# Magnetic-Encoder-V01.net
KiCad netlist of a schematic drawn in Altium Designer
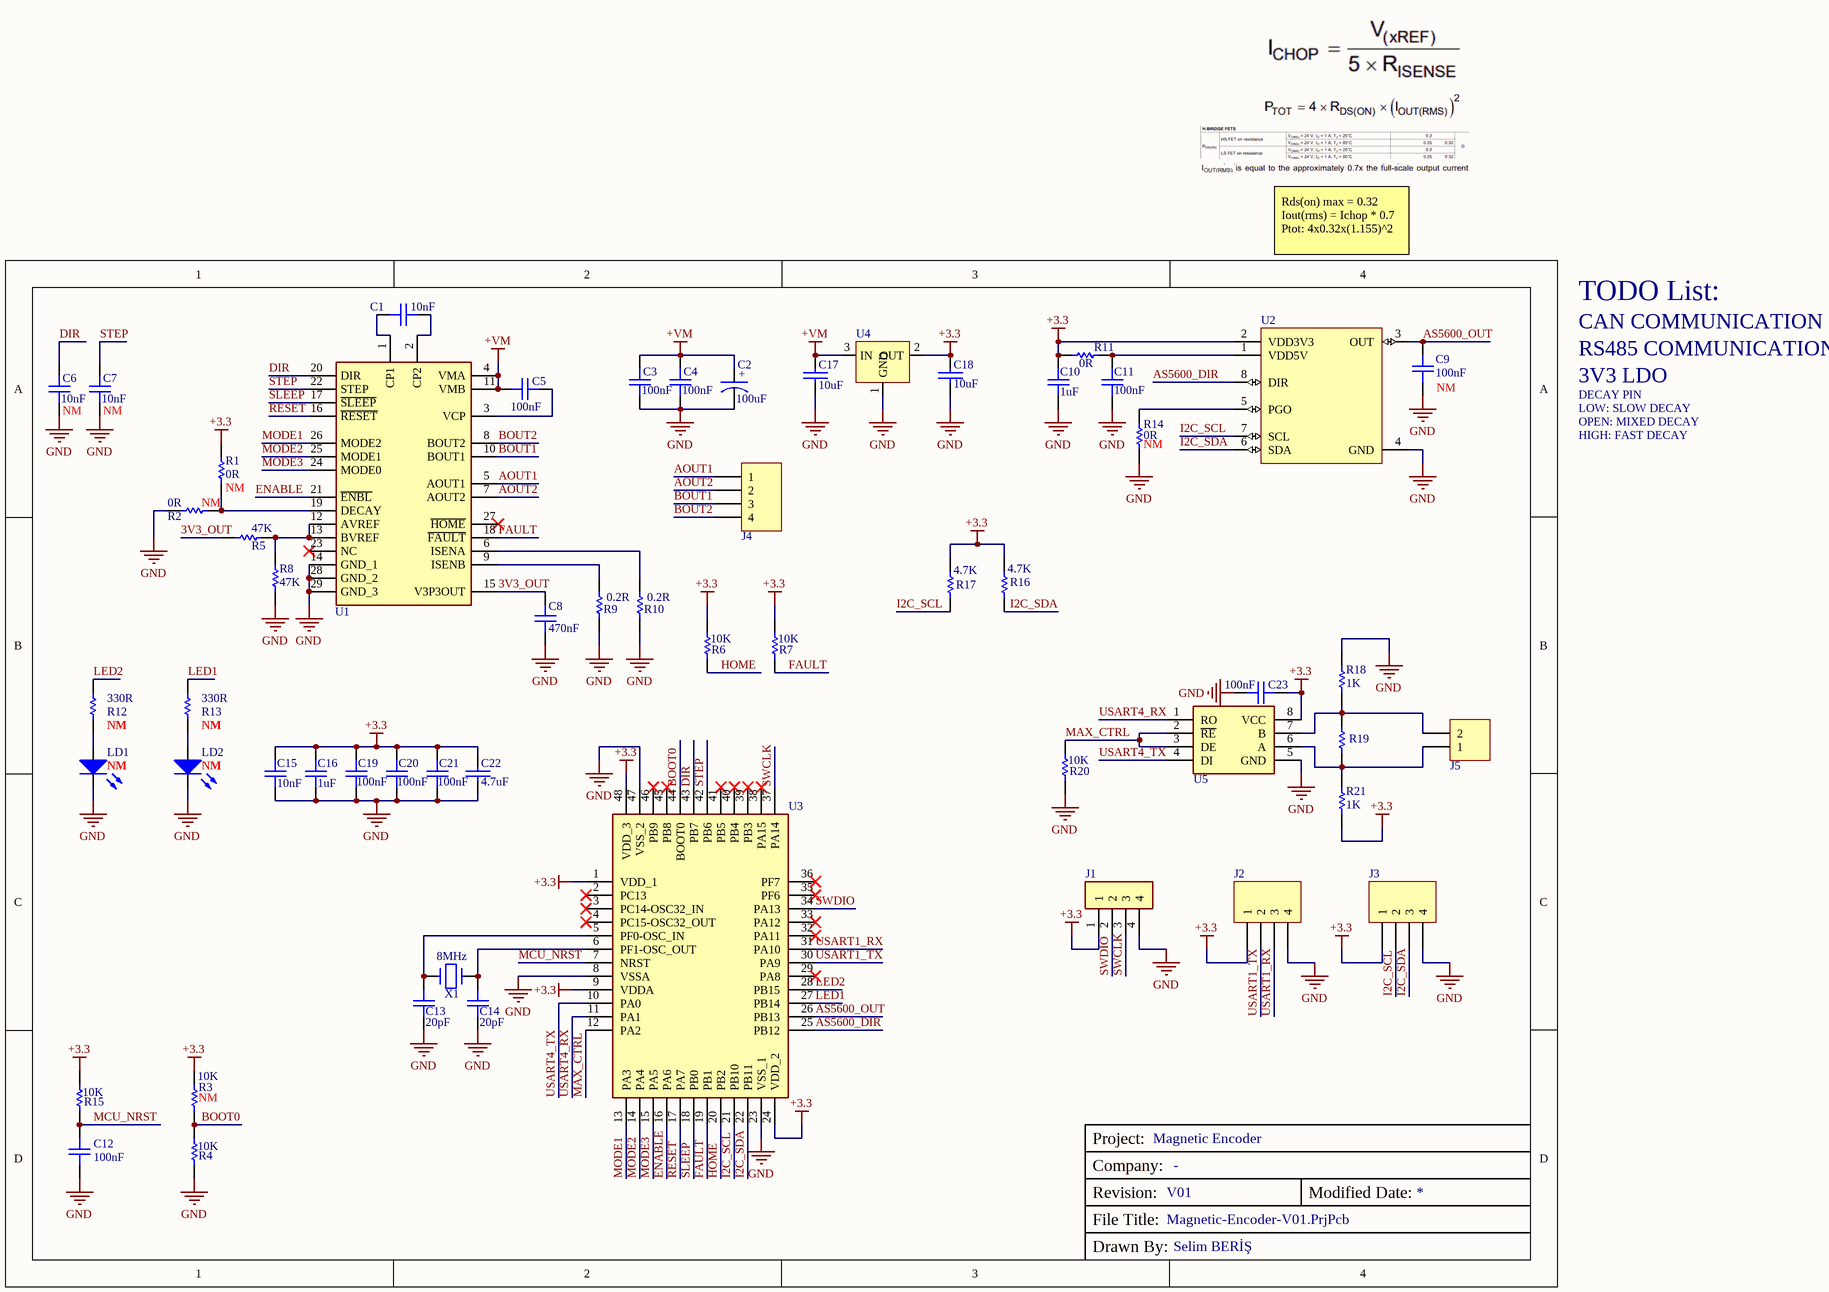
[diagram p0: Magnetic-Encoder-V01.SchDoc]

(export (version "E")
  (design (tool "Eeschema 10.0.6"))
  (components
    (comp (ref "C1")
      (value "10nF")
      (footprint "Cap-0603")
      (description "MLCC (1608) 0603 10nF 50VDC ±10% X7R")
      (fields (field (name "VOLTAGE") "50V") (field (name "TOLERANCE") "%10"))
      (libsource (lib "Components") (part "Capacitor_0603"))
    )
    (comp (ref "C2")
      (value "100uF")
      (footprint "MRW-025V101ME077-T/R")
      (description "CAP.EL.100uF 25V 6.3x7.7 105C 2000Hrs SMD")
      (fields (field (name "VOLTAGE") "25V") (field (name "TOLERANCE") "%20"))
      (libsource (lib "Components") (part "MRW-025V101ME077-T/R"))
    )
    (comp (ref "C3")
      (value "100nF")
      (footprint "Cap-0603")
      (description "MLCC (1608) 0603 100nF 50VDC ±10% X7R")
      (fields (field (name "VOLTAGE") "50V") (field (name "TOLERANCE") "%10"))
      (libsource (lib "Components") (part "Capacitor_0603"))
    )
    (comp (ref "C4")
      (value "100nF")
      (footprint "Cap-0603")
      (description "MLCC (1608) 0603 100nF 50VDC ±10% X7R")
      (fields (field (name "VOLTAGE") "50V") (field (name "TOLERANCE") "%10"))
      (libsource (lib "Components") (part "Capacitor_0603"))
    )
    (comp (ref "C5")
      (value "100nF")
      (footprint "Cap-0603")
      (description "MLCC (1608) 0603 100nF 50VDC ±10% X7R")
      (fields (field (name "VOLTAGE") "50V") (field (name "TOLERANCE") "%10"))
      (libsource (lib "Components") (part "Capacitor_0603"))
    )
    (comp (ref "C6")
      (value "10nF")
      (footprint "Cap-0603")
      (description "MLCC (1608) 0603 10nF 50VDC ±10% X7R")
      (fields (field (name "VOLTAGE") "50V") (field (name "TOLERANCE") "%10") (field (name "PROCESS") "NM"))
      (libsource (lib "Components") (part "Capacitor_0603"))
    )
    (comp (ref "C7")
      (value "10nF")
      (footprint "Cap-0603")
      (description "MLCC (1608) 0603 10nF 50VDC ±10% X7R")
      (fields (field (name "VOLTAGE") "50V") (field (name "TOLERANCE") "%10") (field (name "PROCESS") "NM"))
      (libsource (lib "Components") (part "Capacitor_0603"))
    )
    (comp (ref "C8")
      (value "470nF")
      (footprint "Cap-0603")
      (description "MLCC (1608) 0603 470nF 25VDC ±10% X7R")
      (fields (field (name "VOLTAGE") "25V") (field (name "TOLERANCE") "%10"))
      (libsource (lib "Components") (part "Capacitor_0603"))
    )
    (comp (ref "C9")
      (value "100nF")
      (footprint "Cap-0603")
      (description "MLCC (1608) 0603 100nF 50VDC ±10% X7R")
      (fields (field (name "VOLTAGE") "50V") (field (name "TOLERANCE") "%10") (field (name "PROCESS") "NM"))
      (libsource (lib "Components") (part "Capacitor_0603"))
    )
    (comp (ref "C10")
      (value "1uF")
      (footprint "Cap-0603")
      (description "MLCC (1608) 0603 1uF 25VDC ±10% X7R")
      (fields (field (name "VOLTAGE") "25V") (field (name "TOLERANCE") "%10"))
      (libsource (lib "Components") (part "Capacitor_0603"))
    )
    (comp (ref "C11")
      (value "100nF")
      (footprint "Cap-0603")
      (description "MLCC (1608) 0603 100nF 50VDC ±10% X7R")
      (fields (field (name "VOLTAGE") "50V") (field (name "TOLERANCE") "%10"))
      (libsource (lib "Components") (part "Capacitor_0603"))
    )
    (comp (ref "C12")
      (value "100nF")
      (footprint "Cap-0603")
      (description "MLCC (1608) 0603 100nF 50VDC ±10% X7R")
      (fields (field (name "VOLTAGE") "50V") (field (name "TOLERANCE") "%10"))
      (libsource (lib "Components") (part "Capacitor_0603"))
    )
    (comp (ref "C13")
      (value "20pF")
      (footprint "Cap-0603")
      (description "MLCC (1608) 0603 20pF 50VDC ±5% C0G (NP0)")
      (fields (field (name "VOLTAGE") "50V") (field (name "TOLERANCE") "%10"))
      (libsource (lib "Components") (part "Capacitor_0603"))
    )
    (comp (ref "C14")
      (value "20pF")
      (footprint "Cap-0603")
      (description "MLCC (1608) 0603 20pF 50VDC ±5% C0G (NP0)")
      (fields (field (name "VOLTAGE") "50V") (field (name "TOLERANCE") "%10"))
      (libsource (lib "Components") (part "Capacitor_0603"))
    )
    (comp (ref "C15")
      (value "10nF")
      (footprint "Cap-0603")
      (description "MLCC (1608) 0603 10nF 50VDC ±10% X7R")
      (fields (field (name "VOLTAGE") "50V") (field (name "TOLERANCE") "%10"))
      (libsource (lib "Components") (part "Capacitor_0603"))
    )
    (comp (ref "C16")
      (value "1uF")
      (footprint "Cap-0603")
      (description "MLCC (1608) 0603 1uF 25VDC ±10% X7R")
      (fields (field (name "VOLTAGE") "25V") (field (name "TOLERANCE") "%10"))
      (libsource (lib "Components") (part "Capacitor_0603"))
    )
    (comp (ref "C17")
      (value "10uF")
      (footprint "Cap-0805")
      (description "MLCC (2012) 0805 10uF 25VDC ±10% X5R")
      (fields (field (name "TOLERANCE") "%10") (field (name "VOLTAGE") "25V"))
      (libsource (lib "Components") (part "Capacitor_0805"))
    )
    (comp (ref "C18")
      (value "10uF")
      (footprint "Cap-0805")
      (description "MLCC (2012) 0805 10uF 25VDC ±10% X5R")
      (fields (field (name "TOLERANCE") "%10") (field (name "VOLTAGE") "25V"))
      (libsource (lib "Components") (part "Capacitor_0805"))
    )
    (comp (ref "C19")
      (value "100nF")
      (footprint "Cap-0603")
      (description "MLCC (1608) 0603 100nF 50VDC ±10% X7R")
      (fields (field (name "VOLTAGE") "50V") (field (name "TOLERANCE") "%10"))
      (libsource (lib "Components") (part "Capacitor_0603"))
    )
    (comp (ref "C20")
      (value "100nF")
      (footprint "Cap-0603")
      (description "MLCC (1608) 0603 100nF 50VDC ±10% X7R")
      (fields (field (name "VOLTAGE") "50V") (field (name "TOLERANCE") "%10"))
      (libsource (lib "Components") (part "Capacitor_0603"))
    )
    (comp (ref "C21")
      (value "100nF")
      (footprint "Cap-0603")
      (description "MLCC (1608) 0603 100nF 50VDC ±10% X7R")
      (fields (field (name "VOLTAGE") "50V") (field (name "TOLERANCE") "%10"))
      (libsource (lib "Components") (part "Capacitor_0603"))
    )
    (comp (ref "C22")
      (value "4.7uF")
      (footprint "Cap-0805")
      (description "MLCC (2012) 0805 4.7uF 25VDC ±10% X5R")
      (fields (field (name "TOLERANCE") "%10") (field (name "VOLTAGE") "25V"))
      (libsource (lib "Components") (part "Capacitor_0805"))
    )
    (comp (ref "C23")
      (value "100nF")
      (footprint "Cap-0603")
      (description "MLCC (1608) 0603 100nF 50VDC ±10% X7R")
      (fields (field (name "VOLTAGE") "50V") (field (name "TOLERANCE") "%10"))
      (libsource (lib "Components") (part "Capacitor_0603"))
    )
    (comp (ref "J1")
      (value "Header")
      (footprint "Header(M)_4PIN_2.54MM")
      (description "Header 4-Pin Male 2.54mm Pitch")
      (libsource (lib "Components") (part "Header(M)_4PIN_2.54MM"))
    )
    (comp (ref "J2")
      (value "Connector")
      (footprint "Connector_4_PIN_2.5MM")
      (description "Connector Header Through Hole 4 position 0.098\" (2.50mm)")
      (fields (field (name "PART NUMBER") "353120460"))
      (libsource (lib "") (part "353120460_1"))
    )
    (comp (ref "J3")
      (value "Connector")
      (footprint "Connector_4_PIN_2.5MM")
      (description "Connector Header Through Hole 4 position 0.098\" (2.50mm)")
      (fields (field (name "PART NUMBER") "353120460"))
      (libsource (lib "") (part "353120460_1"))
    )
    (comp (ref "J4")
      (value "Connector")
      (footprint "Connector_4_PIN_2.5MM")
      (description "Connector Header Through Hole 4 position 0.098\" (2.50mm)")
      (fields (field (name "PART NUMBER") "353120460"))
      (libsource (lib "Components") (part "353120460"))
    )
    (comp (ref "J5")
      (value "Klemens")
      (footprint "DG1285002P14")
      (description "TERM.BLK.5.00MM 2P PCB TYPE 1 BOY GREEN")
      (fields (field (name "PART NUMBER") "DG128-5.0-02P-14-00AH"))
      (libsource (lib "Components") (part "Klemens_2PIN_VIDA"))
    )
    (comp (ref "LD1")
      (value "LED")
      (footprint "LED_0603")
      (description "LED - Discrete 0603 (1608 Metric)")
      (fields (field (name "PART NUMBER") "LTST-C190KRKT") (field (name "PROCESS") "NM"))
      (libsource (lib "Components") (part "LED_0603"))
    )
    (comp (ref "LD2")
      (value "LED")
      (footprint "LED_0603")
      (description "LED - Discrete 0603 (1608 Metric)")
      (fields (field (name "PART NUMBER") "LTST-C190KRKT") (field (name "PROCESS") "NM"))
      (libsource (lib "Components") (part "LED_0603"))
    )
    (comp (ref "R1")
      (value "0R")
      (footprint "RES-0603")
      (description "RES.(1608) 0603 0 Ohms 5% 1/10W-S")
      (fields (field (name "POWER") "1/10W") (field (name "TOLERANCE") "%5") (field (name "PROCESS") "NM"))
      (libsource (lib "Components") (part "Resistor_0603"))
    )
    (comp (ref "R2")
      (value "0R")
      (footprint "RES-0603")
      (description "RES.(1608) 0603 0 Ohms 5% 1/10W-S")
      (fields (field (name "POWER") "1/10W") (field (name "TOLERANCE") "%5") (field (name "PROCESS") "NM"))
      (libsource (lib "Components") (part "Resistor_0603"))
    )
    (comp (ref "R3")
      (value "10K")
      (footprint "RES-0603")
      (description "RES.(1608) 0603 10K Ohms 5% 1/10W AUTOMOTIV")
      (fields
        (field (name "PROCESS") "NM")
        (field (name "PART NUMBER") "CQ03SAJ0103T5E")
        (field (name "TOLERANCE") "%5")
      )
      (libsource (lib "Components") (part "Resistor_0603"))
    )
    (comp (ref "R4")
      (value "10K")
      (footprint "RES-0603")
      (description "RES.(1608) 0603 10K Ohms 5% 1/10W AUTOMOTIV")
      (fields (field (name "PART NUMBER") "CQ03SAJ0103T5E") (field (name "TOLERANCE") "%5"))
      (libsource (lib "Components") (part "Resistor_0603"))
    )
    (comp (ref "R5")
      (value "47K")
      (footprint "RES-0603")
      (description "RES.(1608) 0603 47K Ohms 5% 1/10W-S")
      (fields (field (name "POWER") "1/10W") (field (name "TOLERANCE") "%5"))
      (libsource (lib "Components") (part "Resistor_0603"))
    )
    (comp (ref "R6")
      (value "10K")
      (footprint "RES-0603")
      (description "RES.(1608) 0603 10K Ohms 5% 1/10W AUTOMOTIV")
      (fields (field (name "PART NUMBER") "CQ03SAJ0103T5E") (field (name "TOLERANCE") "%5"))
      (libsource (lib "Components") (part "Resistor_0603"))
    )
    (comp (ref "R7")
      (value "10K")
      (footprint "RES-0603")
      (description "RES.(1608) 0603 10K Ohms 5% 1/10W AUTOMOTIV")
      (fields (field (name "PART NUMBER") "CQ03SAJ0103T5E") (field (name "TOLERANCE") "%5"))
      (libsource (lib "Components") (part "Resistor_0603"))
    )
    (comp (ref "R8")
      (value "47K")
      (footprint "RES-0603")
      (description "RES.(1608) 0603 47K Ohms 5% 1/10W-S")
      (fields (field (name "POWER") "1/10W") (field (name "TOLERANCE") "%5"))
      (libsource (lib "Components") (part "Resistor_0603"))
    )
    (comp (ref "R9")
      (value "0.2R")
      (footprint "RES-0603")
      (description "RES.(1608) 0603 200m Ohms 1% 1/5W")
      (fields (field (name "PART NUMBER") "CQ03SAJ0103T5E") (field (name "TOLERANCE") "%1"))
      (libsource (lib "Components") (part "Resistor_0603"))
    )
    (comp (ref "R10")
      (value "0.2R")
      (footprint "RES-0603")
      (description "RES.(1608) 0603 200m Ohms 1% 1/5W")
      (fields (field (name "PART NUMBER") "CQ03SAJ0103T5E") (field (name "TOLERANCE") "%1"))
      (libsource (lib "Components") (part "Resistor_0603"))
    )
    (comp (ref "R11")
      (value "0R")
      (footprint "RES-0603")
      (description "RES.(1608) 0603 0 Ohms 5% 1/10W-S")
      (fields (field (name "POWER") "1/10W") (field (name "TOLERANCE") "%5"))
      (libsource (lib "Components") (part "Resistor_0603"))
    )
    (comp (ref "R12")
      (value "330R")
      (footprint "RES-0603")
      (description "RES.(1608) 0603 330 Ohms 1% 1/10W AEC-Q200")
      (fields (field (name "POWER") "1/10W") (field (name "TOLERANCE") "%1") (field (name "PROCESS") "NM"))
      (libsource (lib "Components") (part "Resistor_0603"))
    )
    (comp (ref "R13")
      (value "330R")
      (footprint "RES-0603")
      (description "RES.(1608) 0603 330 Ohms 1% 1/10W AEC-Q200")
      (fields (field (name "POWER") "1/10W") (field (name "TOLERANCE") "%1") (field (name "PROCESS") "NM"))
      (libsource (lib "Components") (part "Resistor_0603"))
    )
    (comp (ref "R14")
      (value "0R")
      (footprint "RES-0603")
      (description "RES.(1608) 0603 0 Ohms 5% 1/10W-S")
      (fields (field (name "POWER") "1/10W") (field (name "TOLERANCE") "%5") (field (name "PROCESS") "NM"))
      (libsource (lib "Components") (part "Resistor_0603"))
    )
    (comp (ref "R15")
      (value "10K")
      (footprint "RES-0603")
      (description "RES.(1608) 0603 10K Ohms 5% 1/10W AUTOMOTIV")
      (fields (field (name "PART NUMBER") "CQ03SAJ0103T5E") (field (name "TOLERANCE") "%5"))
      (libsource (lib "Components") (part "Resistor_0603"))
    )
    (comp (ref "R16")
      (value "4.7K")
      (footprint "RES-0603")
      (description "RES.(1608) 0603 4.7K Ohms 1% 1/10W")
      (fields (field (name "POWER") "1/10W") (field (name "TOLERANCE") "%5"))
      (libsource (lib "Components") (part "Resistor_0603"))
    )
    (comp (ref "R17")
      (value "4.7K")
      (footprint "RES-0603")
      (description "RES.(1608) 0603 4.7K Ohms 1% 1/10W")
      (fields (field (name "POWER") "1/10W") (field (name "TOLERANCE") "%5"))
      (libsource (lib "Components") (part "Resistor_0603"))
    )
    (comp (ref "R18")
      (value "1K")
      (footprint "Resistor_0603")
      (description "RES.(1608) 0603 1K Ohms 5% 1/10W 100PPM SMT")
      (fields (field (name "POWER") "1/10W") (field (name "TOLERANCE") "%5"))
      (libsource (lib "Components_") (part "Resistor"))
    )
    (comp (ref "R19")
      (value "Resistor")
      (footprint "RES-0603")
      (description "RES.(1608) 0603 120 Ohms 1% 1/10W-S 100PPM")
      (fields (field (name "PART NUMBER") "0603SAF1200T5E") (field (name "TOLERANCE") "%1"))
      (libsource (lib "Components") (part "Resistor_0603"))
    )
    (comp (ref "R20")
      (value "10K")
      (footprint "RES-0603")
      (description "RES.(1608) 0603 10K Ohms 5% 1/10W AUTOMOTIV")
      (fields (field (name "PART NUMBER") "CQ03SAJ0103T5E") (field (name "TOLERANCE") "%5"))
      (libsource (lib "Components") (part "Resistor_0603"))
    )
    (comp (ref "R21")
      (value "1K")
      (footprint "Resistor_0603")
      (description "RES.(1608) 0603 1K Ohms 5% 1/10W 100PPM SMT")
      (fields (field (name "POWER") "1/10W") (field (name "TOLERANCE") "%5"))
      (libsource (lib "Components_") (part "Resistor"))
    )
    (comp (ref "U1")
      (value "Motor Driver")
      (footprint "HTSSOP-28")
      (description "Bipolar Motor Driver Power MOSFET Logic 28-HTSSOP")
      (fields (field (name "PART NUMBER") "DRV8825PWPR"))
      (libsource (lib "Components") (part "DRV8825PWPR"))
    )
    (comp (ref "U2")
      (value "Magnetic Encoder")
      (footprint "SOIC 8")
      (description "Hall Effect Sensor Angle External Magnet, Not Included Gull Wing")
      (fields (field (name "PART NUMBER") "AS5600"))
      (libsource (lib "Components") (part "AS5600"))
    )
    (comp (ref "U3")
      (value "Microcontroller")
      (footprint "LQFP-48")
      (fields (field (name "PART NUMBER") "STM32F030C8T6"))
      (libsource (lib "Components") (part "STM32F030C8T6"))
    )
    (comp (ref "U4")
      (value "Voltage Regulator")
      (footprint "SOT223-3")
      (description "IC-1117 V.REG. 1A 3V3 SOT223 SMD AMS")
      (fields (field (name "PART NUMBER") "AMS1117-3.3"))
      (libsource (lib "Components") (part "AMS1117-3.3"))
    )
    (comp (ref "U5")
      (value "Transceiver")
      (footprint "SOIC 8")
      (description "IC-3485 TRANSCEIVER RS-485/RS-422 SOP-8")
      (fields (field (name "PART NUMBER") "MAX3485ED-HTC"))
      (libsource (lib "Components") (part "MAX3485ED-HTC"))
    )
    (comp (ref "X1")
      (value "Crystal")
      (footprint "HC-49SD")
      (description "CRYSTAL 8MHz HC49SMT 20pF SMD TR RALTRON")
      (fields (field (name "FREQUENCY") "8MHz") (field (name "PART NUMBER") "AS-8.000-20-SMD-TR"))
      (libsource (lib "Components") (part "Crystal_SMD_2"))
    )
  )
  (nets
    (net (code "1") (name "+3.3") (class "Default")
      (node (ref "C10") (pin "2") (pinfunction "2_2") (pintype "passive"))
      (node (ref "C15") (pin "2") (pinfunction "2_2") (pintype "passive"))
      (node (ref "C16") (pin "2") (pinfunction "2_2") (pintype "passive"))
      (node (ref "C18") (pin "1") (pintype "passive"))
      (node (ref "C19") (pin "2") (pinfunction "2_2") (pintype "passive"))
      (node (ref "C20") (pin "2") (pinfunction "2_2") (pintype "passive"))
      (node (ref "C21") (pin "2") (pinfunction "2_2") (pintype "passive"))
      (node (ref "C22") (pin "1") (pintype "passive"))
      (node (ref "C23") (pin "1") (pinfunction "1_1") (pintype "passive"))
      (node (ref "J1") (pin "1") (pinfunction "1_1") (pintype "passive"))
      (node (ref "J2") (pin "1") (pinfunction "1_1") (pintype "passive"))
      (node (ref "J3") (pin "1") (pinfunction "1_1") (pintype "passive"))
      (node (ref "R1") (pin "1") (pinfunction "1_1") (pintype "passive"))
      (node (ref "R11") (pin "2") (pinfunction "2_2") (pintype "passive"))
      (node (ref "R15") (pin "2") (pinfunction "2_2") (pintype "passive"))
      (node (ref "R16") (pin "2") (pinfunction "2_2") (pintype "passive"))
      (node (ref "R17") (pin "2") (pinfunction "2_2") (pintype "passive"))
      (node (ref "R21") (pin "2") (pinfunction "2_2") (pintype "passive"))
      (node (ref "R3") (pin "2") (pinfunction "2_2") (pintype "passive"))
      (node (ref "R6") (pin "1") (pinfunction "1_1") (pintype "passive"))
      (node (ref "R7") (pin "1") (pinfunction "1_1") (pintype "passive"))
      (node (ref "U2") (pin "2") (pinfunction "VDD3V3_2") (pintype "power_in"))
      (node (ref "U3") (pin "1") (pinfunction "VDD_1_1") (pintype "passive"))
      (node (ref "U3") (pin "24") (pinfunction "VDD_2_24") (pintype "passive"))
      (node (ref "U3") (pin "48") (pinfunction "VDD_3_48") (pintype "passive"))
      (node (ref "U3") (pin "9") (pinfunction "VDDA_9") (pintype "passive"))
      (node (ref "U4") (pin "2") (pinfunction "OUT_2") (pintype "power_in"))
      (node (ref "U5") (pin "8") (pinfunction "VCC_8") (pintype "passive"))
    )
    (net (code "2") (name "+VM") (class "Default")
      (node (ref "C17") (pin "1") (pintype "passive"))
      (node (ref "C2") (pin "1") (pinfunction "1_1") (pintype "passive"))
      (node (ref "C3") (pin "1") (pinfunction "1_1") (pintype "passive"))
      (node (ref "C4") (pin "1") (pinfunction "1_1") (pintype "passive"))
      (node (ref "C5") (pin "1") (pinfunction "1_1") (pintype "passive"))
      (node (ref "U1") (pin "11") (pinfunction "VMB_11") (pintype "passive"))
      (node (ref "U1") (pin "4") (pinfunction "VMA_4") (pintype "passive"))
      (node (ref "U4") (pin "3") (pinfunction "IN_3") (pintype "power_in"))
    )
    (net (code "3") (name "/3V3_OUT") (class "Default")
      (node (ref "C8") (pin "1") (pinfunction "1_1") (pintype "passive"))
      (node (ref "R5") (pin "2") (pinfunction "2_2") (pintype "passive"))
      (node (ref "U1") (pin "15") (pinfunction "V3P3OUT_15") (pintype "passive"))
    )
    (net (code "4") (name "/AOUT1") (class "Default")
      (node (ref "J4") (pin "1") (pinfunction "1_1") (pintype "passive"))
      (node (ref "U1") (pin "5") (pinfunction "AOUT1_5") (pintype "passive"))
    )
    (net (code "5") (name "/AOUT2") (class "Default")
      (node (ref "J4") (pin "2") (pinfunction "2_2") (pintype "passive"))
      (node (ref "U1") (pin "7") (pinfunction "AOUT2_7") (pintype "passive"))
    )
    (net (code "6") (name "/AS5600_DIR") (class "Default")
      (node (ref "U2") (pin "8") (pinfunction "DIR_8") (pintype "bidirectional"))
      (node (ref "U3") (pin "25") (pinfunction "PB12_25") (pintype "passive"))
    )
    (net (code "7") (name "/AS5600_OUT") (class "Default")
      (node (ref "C9") (pin "2") (pinfunction "2_2") (pintype "passive"))
      (node (ref "U2") (pin "3") (pinfunction "OUT_3") (pintype "bidirectional"))
      (node (ref "U3") (pin "26") (pinfunction "PB13_26") (pintype "passive"))
    )
    (net (code "8") (name "/BOOT0") (class "Default")
      (node (ref "R3") (pin "1") (pinfunction "1_1") (pintype "passive"))
      (node (ref "R4") (pin "2") (pinfunction "2_2") (pintype "passive"))
      (node (ref "U3") (pin "44") (pinfunction "BOOT0_44") (pintype "passive"))
    )
    (net (code "9") (name "/BOUT1") (class "Default")
      (node (ref "J4") (pin "3") (pinfunction "3_3") (pintype "passive"))
      (node (ref "U1") (pin "10") (pinfunction "BOUT1_10") (pintype "passive"))
    )
    (net (code "10") (name "/BOUT2") (class "Default")
      (node (ref "J4") (pin "4") (pinfunction "4_4") (pintype "passive"))
      (node (ref "U1") (pin "8") (pinfunction "BOUT2_8") (pintype "passive"))
    )
    (net (code "11") (name "/DIR") (class "Default")
      (node (ref "C6") (pin "1") (pinfunction "1_1") (pintype "passive"))
      (node (ref "U1") (pin "20") (pinfunction "DIR_20") (pintype "passive"))
      (node (ref "U3") (pin "43") (pinfunction "PB7_43") (pintype "passive"))
    )
    (net (code "12") (name "/ENABLE") (class "Default")
      (node (ref "U1") (pin "21") (pinfunction "~{ENBL}_21") (pintype "passive"))
      (node (ref "U3") (pin "16") (pinfunction "PA6_16") (pintype "passive"))
    )
    (net (code "13") (name "/FAULT") (class "Default")
      (node (ref "R7") (pin "2") (pinfunction "2_2") (pintype "passive"))
      (node (ref "U1") (pin "18") (pinfunction "~{FAULT}_18") (pintype "passive"))
      (node (ref "U3") (pin "19") (pinfunction "PB1_19") (pintype "passive"))
    )
    (net (code "14") (name "/HOME") (class "Default")
      (node (ref "R6") (pin "2") (pinfunction "2_2") (pintype "passive"))
      (node (ref "U3") (pin "20") (pinfunction "PB2_20") (pintype "passive"))
    )
    (net (code "15") (name "/I2C_SCL") (class "Default")
      (node (ref "J3") (pin "2") (pinfunction "2_2") (pintype "passive"))
      (node (ref "R17") (pin "1") (pinfunction "1_1") (pintype "passive"))
      (node (ref "U2") (pin "7") (pinfunction "SCL_7") (pintype "bidirectional"))
      (node (ref "U3") (pin "21") (pinfunction "PB10_21") (pintype "passive"))
    )
    (net (code "16") (name "/I2C_SDA") (class "Default")
      (node (ref "J3") (pin "3") (pinfunction "3_3") (pintype "passive"))
      (node (ref "R16") (pin "1") (pinfunction "1_1") (pintype "passive"))
      (node (ref "U2") (pin "6") (pinfunction "SDA_6") (pintype "bidirectional"))
      (node (ref "U3") (pin "22") (pinfunction "PB11_22") (pintype "passive"))
    )
    (net (code "17") (name "/LED1") (class "Default")
      (node (ref "R13") (pin "2") (pinfunction "2_2") (pintype "passive"))
      (node (ref "U3") (pin "27") (pinfunction "PB14_27") (pintype "passive"))
    )
    (net (code "18") (name "/LED2") (class "Default")
      (node (ref "R12") (pin "2") (pinfunction "2_2") (pintype "passive"))
      (node (ref "U3") (pin "28") (pinfunction "PB15_28") (pintype "passive"))
    )
    (net (code "19") (name "/MAX_CTRL") (class "Default")
      (node (ref "R20") (pin "1") (pinfunction "1_1") (pintype "passive"))
      (node (ref "U3") (pin "12") (pinfunction "PA2_12") (pintype "passive"))
      (node (ref "U5") (pin "2") (pinfunction "~{RE}_2") (pintype "passive"))
      (node (ref "U5") (pin "3") (pinfunction "DE_3") (pintype "passive"))
    )
    (net (code "20") (name "/MCU_NRST") (class "Default")
      (node (ref "C12") (pin "1") (pinfunction "1_1") (pintype "passive"))
      (node (ref "R15") (pin "1") (pinfunction "1_1") (pintype "passive"))
      (node (ref "U3") (pin "7") (pinfunction "NRST_7") (pintype "passive"))
    )
    (net (code "21") (name "/MODE1") (class "Default")
      (node (ref "U1") (pin "26") (pinfunction "MODE2_26") (pintype "passive"))
      (node (ref "U3") (pin "13") (pinfunction "PA3_13") (pintype "passive"))
    )
    (net (code "22") (name "/MODE2") (class "Default")
      (node (ref "U1") (pin "25") (pinfunction "MODE1_25") (pintype "passive"))
      (node (ref "U3") (pin "14") (pinfunction "PA4_14") (pintype "passive"))
    )
    (net (code "23") (name "/MODE3") (class "Default")
      (node (ref "U1") (pin "24") (pinfunction "MODE0_24") (pintype "passive"))
      (node (ref "U3") (pin "15") (pinfunction "PA5_15") (pintype "passive"))
    )
    (net (code "24") (name "/RESET") (class "Default")
      (node (ref "U1") (pin "16") (pinfunction "~{RESET}_16") (pintype "passive"))
      (node (ref "U3") (pin "17") (pinfunction "PA7_17") (pintype "passive"))
    )
    (net (code "25") (name "/SLEEP") (class "Default")
      (node (ref "U1") (pin "17") (pinfunction "~{SLEEP}_17") (pintype "passive"))
      (node (ref "U3") (pin "18") (pinfunction "PB0_18") (pintype "passive"))
    )
    (net (code "26") (name "/STEP") (class "Default")
      (node (ref "C7") (pin "2") (pinfunction "2_2") (pintype "passive"))
      (node (ref "U1") (pin "22") (pinfunction "STEP_22") (pintype "passive"))
      (node (ref "U3") (pin "42") (pinfunction "PB6_42") (pintype "passive"))
    )
    (net (code "27") (name "/SWCLK") (class "Default")
      (node (ref "J1") (pin "3") (pinfunction "3_3") (pintype "passive"))
      (node (ref "U3") (pin "37") (pinfunction "PA14_37") (pintype "passive"))
    )
    (net (code "28") (name "/SWDIO") (class "Default")
      (node (ref "J1") (pin "2") (pinfunction "2_2") (pintype "passive"))
      (node (ref "U3") (pin "34") (pinfunction "PA13_34") (pintype "passive"))
    )
    (net (code "29") (name "/USART1_RX") (class "Default")
      (node (ref "J2") (pin "3") (pinfunction "3_3") (pintype "passive"))
      (node (ref "U3") (pin "31") (pinfunction "PA10_31") (pintype "passive"))
    )
    (net (code "30") (name "/USART1_TX") (class "Default")
      (node (ref "J2") (pin "2") (pinfunction "2_2") (pintype "passive"))
      (node (ref "U3") (pin "30") (pinfunction "PA9_30") (pintype "passive"))
    )
    (net (code "31") (name "/USART4_RX") (class "Default")
      (node (ref "U3") (pin "11") (pinfunction "PA1_11") (pintype "passive"))
      (node (ref "U5") (pin "1") (pinfunction "RO_1") (pintype "passive"))
    )
    (net (code "32") (name "/USART4_TX") (class "Default")
      (node (ref "U3") (pin "10") (pinfunction "PA0_10") (pintype "passive"))
      (node (ref "U5") (pin "4") (pinfunction "DI_4") (pintype "passive"))
    )
    (net (code "33") (name "GND") (class "Default")
      (node (ref "C10") (pin "1") (pinfunction "1_1") (pintype "passive"))
      (node (ref "C11") (pin "1") (pinfunction "1_1") (pintype "passive"))
      (node (ref "C12") (pin "2") (pinfunction "2_2") (pintype "passive"))
      (node (ref "C13") (pin "2") (pinfunction "2_2") (pintype "passive"))
      (node (ref "C14") (pin "2") (pinfunction "2_2") (pintype "passive"))
      (node (ref "C15") (pin "1") (pinfunction "1_1") (pintype "passive"))
      (node (ref "C16") (pin "1") (pinfunction "1_1") (pintype "passive"))
      (node (ref "C17") (pin "2") (pintype "passive"))
      (node (ref "C18") (pin "2") (pintype "passive"))
      (node (ref "C19") (pin "1") (pinfunction "1_1") (pintype "passive"))
      (node (ref "C2") (pin "2") (pinfunction "2_2") (pintype "passive"))
      (node (ref "C20") (pin "1") (pinfunction "1_1") (pintype "passive"))
      (node (ref "C21") (pin "1") (pinfunction "1_1") (pintype "passive"))
      (node (ref "C22") (pin "2") (pintype "passive"))
      (node (ref "C23") (pin "2") (pinfunction "2_2") (pintype "passive"))
      (node (ref "C3") (pin "2") (pinfunction "2_2") (pintype "passive"))
      (node (ref "C4") (pin "2") (pinfunction "2_2") (pintype "passive"))
      (node (ref "C6") (pin "2") (pinfunction "2_2") (pintype "passive"))
      (node (ref "C7") (pin "1") (pinfunction "1_1") (pintype "passive"))
      (node (ref "C8") (pin "2") (pinfunction "2_2") (pintype "passive"))
      (node (ref "C9") (pin "1") (pinfunction "1_1") (pintype "passive"))
      (node (ref "J1") (pin "4") (pinfunction "4_4") (pintype "passive"))
      (node (ref "J2") (pin "4") (pinfunction "4_4") (pintype "passive"))
      (node (ref "J3") (pin "4") (pinfunction "4_4") (pintype "passive"))
      (node (ref "LD1") (pin "2") (pinfunction "2_2") (pintype "passive"))
      (node (ref "LD2") (pin "2") (pinfunction "2_2") (pintype "passive"))
      (node (ref "R10") (pin "1") (pinfunction "1_1") (pintype "passive"))
      (node (ref "R14") (pin "1") (pinfunction "1_1") (pintype "passive"))
      (node (ref "R18") (pin "1") (pinfunction "1_1") (pintype "passive"))
      (node (ref "R2") (pin "2") (pinfunction "2_2") (pintype "passive"))
      (node (ref "R20") (pin "2") (pinfunction "2_2") (pintype "passive"))
      (node (ref "R4") (pin "1") (pinfunction "1_1") (pintype "passive"))
      (node (ref "R8") (pin "2") (pinfunction "2_2") (pintype "passive"))
      (node (ref "R9") (pin "1") (pinfunction "1_1") (pintype "passive"))
      (node (ref "U1") (pin "14") (pinfunction "GND_1_14") (pintype "passive"))
      (node (ref "U1") (pin "28") (pinfunction "GND_2_28") (pintype "passive"))
      (node (ref "U1") (pin "29") (pinfunction "GND_3_29") (pintype "passive"))
      (node (ref "U2") (pin "4") (pinfunction "GND_4") (pintype "power_in"))
      (node (ref "U3") (pin "23") (pinfunction "VSS_1_23") (pintype "passive"))
      (node (ref "U3") (pin "47") (pinfunction "VSS_2_47") (pintype "passive"))
      (node (ref "U3") (pin "8") (pinfunction "VSSA_8") (pintype "passive"))
      (node (ref "U4") (pin "1") (pinfunction "GND_1") (pintype "power_in"))
      (node (ref "U5") (pin "5") (pinfunction "GND_5") (pintype "passive"))
    )
    (net (code "34") (name "Net-(LD1-Pad1)") (class "Default")
      (node (ref "LD1") (pin "1") (pinfunction "1_1") (pintype "passive"))
      (node (ref "R12") (pin "1") (pinfunction "1_1") (pintype "passive"))
    )
    (net (code "35") (name "Net-(LD2-Pad1)") (class "Default")
      (node (ref "LD2") (pin "1") (pinfunction "1_1") (pintype "passive"))
      (node (ref "R13") (pin "1") (pinfunction "1_1") (pintype "passive"))
    )
    (net (code "36") (name "Net-(U1-AVREF)") (class "Default")
      (node (ref "R5") (pin "1") (pinfunction "1_1") (pintype "passive"))
      (node (ref "R8") (pin "1") (pinfunction "1_1") (pintype "passive"))
      (node (ref "U1") (pin "12") (pinfunction "AVREF_12") (pintype "passive"))
      (node (ref "U1") (pin "13") (pinfunction "BVREF_13") (pintype "passive"))
    )
    (net (code "37") (name "Net-(U1-CP1)") (class "Default")
      (node (ref "C1") (pin "1") (pinfunction "1_1") (pintype "passive"))
      (node (ref "U1") (pin "1") (pinfunction "CP1_1") (pintype "passive"))
    )
    (net (code "38") (name "Net-(U1-CP2)") (class "Default")
      (node (ref "C1") (pin "2") (pinfunction "2_2") (pintype "passive"))
      (node (ref "U1") (pin "2") (pinfunction "CP2_2") (pintype "passive"))
    )
    (net (code "39") (name "Net-(U1-DECAY)") (class "Default")
      (node (ref "R1") (pin "2") (pinfunction "2_2") (pintype "passive"))
      (node (ref "R2") (pin "1") (pinfunction "1_1") (pintype "passive"))
      (node (ref "U1") (pin "19") (pinfunction "DECAY_19") (pintype "passive"))
    )
    (net (code "40") (name "Net-(U1-ISENA)") (class "Default")
      (node (ref "R10") (pin "2") (pinfunction "2_2") (pintype "passive"))
      (node (ref "U1") (pin "6") (pinfunction "ISENA_6") (pintype "passive"))
    )
    (net (code "41") (name "Net-(U1-ISENB)") (class "Default")
      (node (ref "R9") (pin "2") (pinfunction "2_2") (pintype "passive"))
      (node (ref "U1") (pin "9") (pinfunction "ISENB_9") (pintype "passive"))
    )
    (net (code "42") (name "Net-(U1-VCP)") (class "Default")
      (node (ref "C5") (pin "2") (pinfunction "2_2") (pintype "passive"))
      (node (ref "U1") (pin "3") (pinfunction "VCP_3") (pintype "passive"))
    )
    (net (code "43") (name "Net-(U2-PGO)") (class "Default")
      (node (ref "R14") (pin "2") (pinfunction "2_2") (pintype "passive"))
      (node (ref "U2") (pin "5") (pinfunction "PGO_5") (pintype "bidirectional"))
    )
    (net (code "44") (name "Net-(U2-VDD5V)") (class "Default")
      (node (ref "C11") (pin "2") (pinfunction "2_2") (pintype "passive"))
      (node (ref "R11") (pin "1") (pinfunction "1_1") (pintype "passive"))
      (node (ref "U2") (pin "1") (pinfunction "VDD5V_1") (pintype "power_in"))
    )
    (net (code "45") (name "Net-(U3-PF0-OSC_IN)") (class "Default")
      (node (ref "C13") (pin "1") (pinfunction "1_1") (pintype "passive"))
      (node (ref "U3") (pin "5") (pinfunction "PF0-OSC_IN_5") (pintype "passive"))
      (node (ref "X1") (pin "1") (pintype "passive"))
    )
    (net (code "46") (name "Net-(U3-PF1-OSC_OUT)") (class "Default")
      (node (ref "C14") (pin "1") (pinfunction "1_1") (pintype "passive"))
      (node (ref "U3") (pin "6") (pinfunction "PF1-OSC_OUT_6") (pintype "passive"))
      (node (ref "X1") (pin "2") (pintype "passive"))
    )
    (net (code "47") (name "Net-(U5-A)") (class "Default")
      (node (ref "J5") (pin "1") (pinfunction "1_1") (pintype "passive"))
      (node (ref "R19") (pin "2") (pinfunction "2_2") (pintype "passive"))
      (node (ref "R21") (pin "1") (pinfunction "1_1") (pintype "passive"))
      (node (ref "U5") (pin "6") (pinfunction "A_6") (pintype "passive"))
    )
    (net (code "48") (name "Net-(U5-B)") (class "Default")
      (node (ref "J5") (pin "2") (pinfunction "2_2") (pintype "passive"))
      (node (ref "R18") (pin "2") (pinfunction "2_2") (pintype "passive"))
      (node (ref "R19") (pin "1") (pinfunction "1_1") (pintype "passive"))
      (node (ref "U5") (pin "7") (pinfunction "B_7") (pintype "passive"))
    )
    (net (code "49") (name "unconnected-(U1-NC-Pad23)") (class "Default")
      (node (ref "U1") (pin "23") (pinfunction "NC_23") (pintype "passive+no_connect"))
    )
    (net (code "50") (name "unconnected-(U1-~{HOME}-Pad27)") (class "Default")
      (node (ref "U1") (pin "27") (pinfunction "~{HOME}_27") (pintype "passive+no_connect"))
    )
    (net (code "51") (name "unconnected-(U3-PA8-Pad29)") (class "Default")
      (node (ref "U3") (pin "29") (pinfunction "PA8_29") (pintype "passive+no_connect"))
    )
    (net (code "52") (name "unconnected-(U3-PA11-Pad32)") (class "Default")
      (node (ref "U3") (pin "32") (pinfunction "PA11_32") (pintype "passive+no_connect"))
    )
    (net (code "53") (name "unconnected-(U3-PA12-Pad33)") (class "Default")
      (node (ref "U3") (pin "33") (pinfunction "PA12_33") (pintype "passive+no_connect"))
    )
    (net (code "54") (name "unconnected-(U3-PA15-Pad38)") (class "Default")
      (node (ref "U3") (pin "38") (pinfunction "PA15_38") (pintype "passive+no_connect"))
    )
    (net (code "55") (name "unconnected-(U3-PB3-Pad39)") (class "Default")
      (node (ref "U3") (pin "39") (pinfunction "PB3_39") (pintype "passive+no_connect"))
    )
    (net (code "56") (name "unconnected-(U3-PB4-Pad40)") (class "Default")
      (node (ref "U3") (pin "40") (pinfunction "PB4_40") (pintype "passive+no_connect"))
    )
    (net (code "57") (name "unconnected-(U3-PB5-Pad41)") (class "Default")
      (node (ref "U3") (pin "41") (pinfunction "PB5_41") (pintype "passive+no_connect"))
    )
    (net (code "58") (name "unconnected-(U3-PB8-Pad45)") (class "Default")
      (node (ref "U3") (pin "45") (pinfunction "PB8_45") (pintype "passive+no_connect"))
    )
    (net (code "59") (name "unconnected-(U3-PB9-Pad46)") (class "Default")
      (node (ref "U3") (pin "46") (pinfunction "PB9_46") (pintype "passive+no_connect"))
    )
    (net (code "60") (name "unconnected-(U3-PC13-Pad2)") (class "Default")
      (node (ref "U3") (pin "2") (pinfunction "PC13_2") (pintype "passive+no_connect"))
    )
    (net (code "61") (name "unconnected-(U3-PC14-OSC32_IN-Pad3)") (class "Default")
      (node (ref "U3") (pin "3") (pinfunction "PC14-OSC32_IN_3") (pintype "passive+no_connect"))
    )
    (net (code "62") (name "unconnected-(U3-PC15-OSC32_OUT-Pad4)") (class "Default")
      (node (ref "U3") (pin "4") (pinfunction "PC15-OSC32_OUT_4") (pintype "passive+no_connect"))
    )
    (net (code "63") (name "unconnected-(U3-PF6-Pad35)") (class "Default")
      (node (ref "U3") (pin "35") (pinfunction "PF6_35") (pintype "passive+no_connect"))
    )
    (net (code "64") (name "unconnected-(U3-PF7-Pad36)") (class "Default")
      (node (ref "U3") (pin "36") (pinfunction "PF7_36") (pintype "passive+no_connect"))
    )
  )
)
